# MPPT.net
KiCad netlist of a schematic drawn in Altium Designer
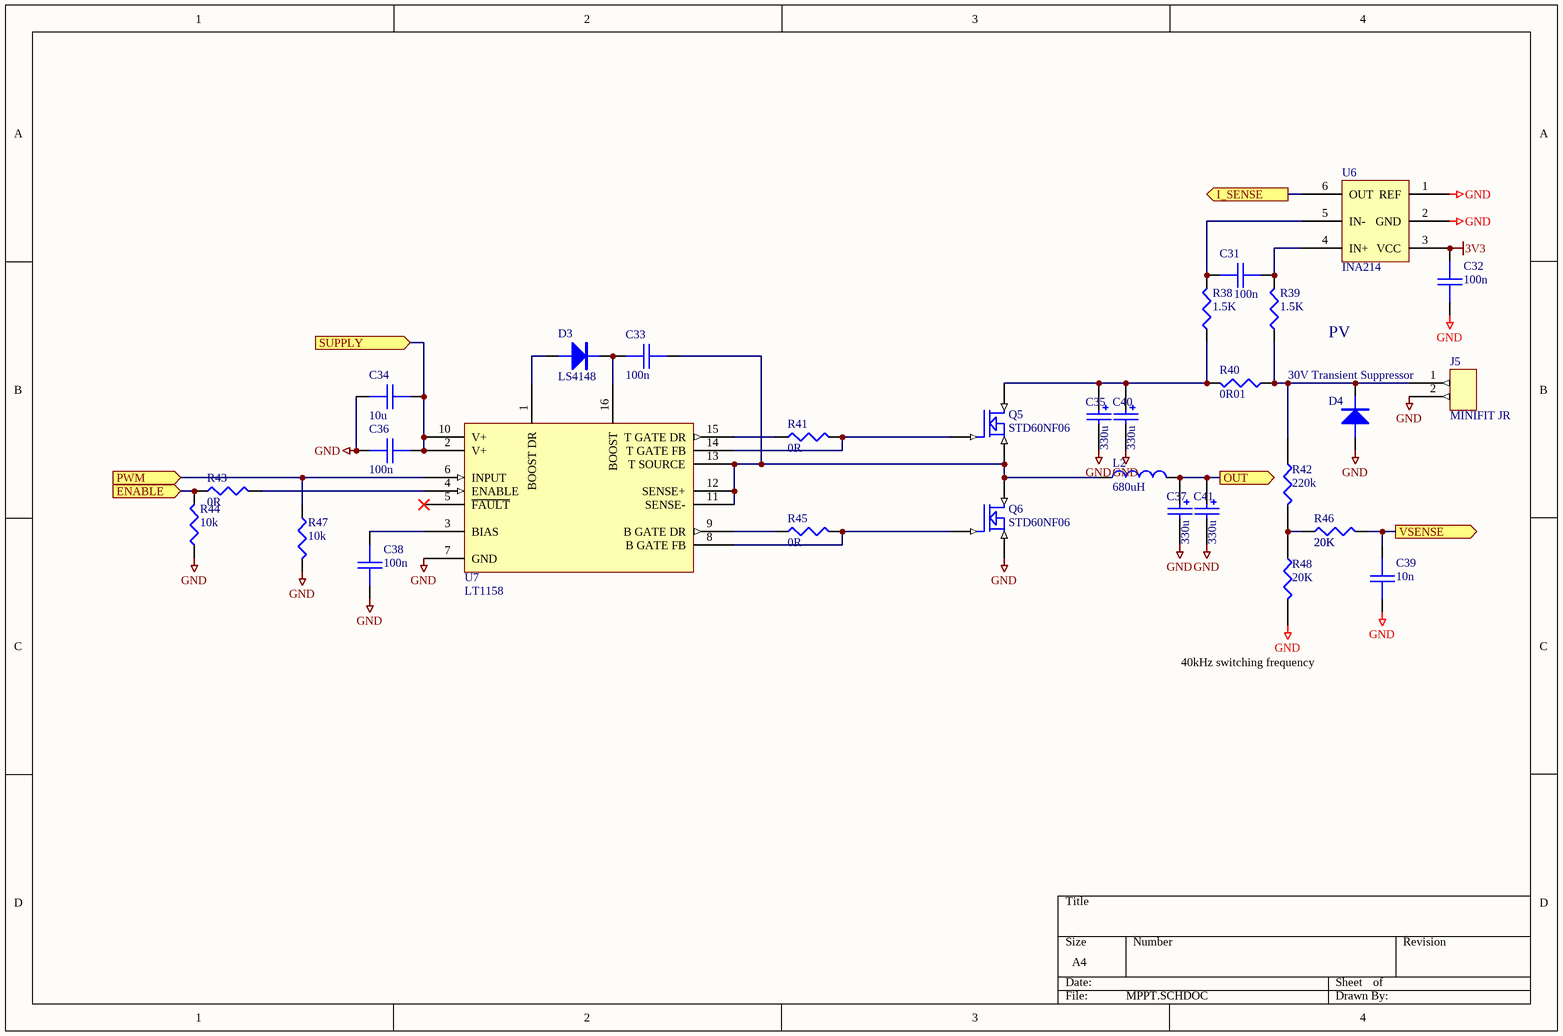
[diagram p0: MPPT.SCHDOC]

(export (version "E")
  (design (tool "Eeschema 10.0.6"))
  (components
    (comp (ref "C31")
      (value "100n")
      (footprint "0603")
      (description "Capacitor")
      (libsource (lib "RCLDQ") (part "CAP"))
    )
    (comp (ref "C32")
      (value "100n")
      (footprint "0603")
      (description "Capacitor")
      (libsource (lib "RCLDQ") (part "CAP"))
    )
    (comp (ref "C33")
      (value "100n")
      (footprint "0603")
      (description "Capacitor")
      (libsource (lib "RCLDQ") (part "CAP"))
    )
    (comp (ref "C34")
      (value "10u")
      (footprint "1206")
      (description "Capacitor")
      (libsource (lib "RCLDQ") (part "CAP"))
    )
    (comp (ref "C35")
      (value "330u")
      (footprint "RAD0.2")
      (description "Polarized Capacitor (Surface Mount)")
      (libsource (lib "RCLDQ") (part "CAP POL3"))
    )
    (comp (ref "C36")
      (value "100n")
      (footprint "0603")
      (description "Capacitor")
      (libsource (lib "RCLDQ") (part "CAP"))
    )
    (comp (ref "C37")
      (value "330u")
      (footprint "RAD0.2")
      (description "Polarized Capacitor (Surface Mount)")
      (libsource (lib "RCLDQ") (part "CAP POL3"))
    )
    (comp (ref "C38")
      (value "100n")
      (footprint "0603")
      (description "Capacitor")
      (libsource (lib "RCLDQ") (part "CAP"))
    )
    (comp (ref "C39")
      (value "10n")
      (footprint "0603")
      (description "Capacitor")
      (libsource (lib "RCLDQ") (part "CAP"))
    )
    (comp (ref "C40")
      (value "330u")
      (footprint "RAD0.2")
      (description "Polarized Capacitor (Surface Mount)")
      (libsource (lib "RCLDQ") (part "CAP POL3"))
    )
    (comp (ref "C41")
      (value "330u")
      (footprint "RAD0.2")
      (description "Polarized Capacitor (Surface Mount)")
      (libsource (lib "RCLDQ") (part "CAP POL3"))
    )
    (comp (ref "D3")
      (value "LS4148")
      (footprint "QMELF")
      (description "Diode")
      (libsource (lib "RCLDQ") (part "DIODE"))
    )
    (comp (ref "D4")
      (value "30V Transient Suppressor")
      (footprint "SMA")
      (description "Diode")
      (libsource (lib "RCLDQ") (part "DIODE"))
    )
    (comp (ref "J5")
      (value "MINIFIT JR")
      (footprint "MINIFITJR-2")
      (libsource (lib "Connectors") (part "CON2"))
    )
    (comp (ref "L2")
      (value "680uH")
      (footprint "Bourns2321-V-RC")
      (description "Inductor")
      (libsource (lib "Miscellaneous Devices") (part "Inductor"))
    )
    (comp (ref "Q5")
      (value "STD60NF06")
      (footprint "DPAK(3)")
      (description "Power MOSFET")
      (libsource (lib "RCLDQ") (part "STD60NF06"))
    )
    (comp (ref "Q6")
      (value "STD60NF06")
      (footprint "DPAK(3)")
      (description "Power MOSFET")
      (libsource (lib "RCLDQ") (part "STD60NF06"))
    )
    (comp (ref "R38")
      (value "1.5K")
      (footprint "0603")
      (description "Resistor")
      (libsource (lib "RCLDQ") (part "RES1"))
    )
    (comp (ref "R39")
      (value "1.5K")
      (footprint "0603")
      (description "Resistor")
      (libsource (lib "RCLDQ") (part "RES1"))
    )
    (comp (ref "R40")
      (value "0R01")
      (footprint "2010")
      (description "Resistor")
      (libsource (lib "RCLDQ") (part "RES1"))
    )
    (comp (ref "R41")
      (value "0R")
      (footprint "0603")
      (description "Resistor")
      (libsource (lib "RCLDQ") (part "RES1"))
    )
    (comp (ref "R42") (value "220k") (footprint "1206") (libsource (lib "*") (part "RES1")))
    (comp (ref "R43")
      (value "0R")
      (footprint "0603")
      (description "Resistor")
      (libsource (lib "RCLDQ") (part "RES1"))
    )
    (comp (ref "R44")
      (value "10k")
      (footprint "0603")
      (description "Resistor")
      (libsource (lib "RCLDQ") (part "RES1"))
    )
    (comp (ref "R45")
      (value "0R")
      (footprint "0603")
      (description "Resistor")
      (libsource (lib "RCLDQ") (part "RES1"))
    )
    (comp (ref "R46")
      (value "20K")
      (footprint "0603")
      (description "Resistor")
      (libsource (lib "RCLDQ") (part "RES1"))
    )
    (comp (ref "R47")
      (value "10k")
      (footprint "0603")
      (description "Resistor")
      (libsource (lib "RCLDQ") (part "RES1"))
    )
    (comp (ref "R48") (value "20K") (footprint "1206") (libsource (lib "*") (part "RES1")))
    (comp (ref "U6")
      (value "INA214")
      (footprint "SC70-6")
      (description "High / Low side Current Sensor")
      (libsource (lib "MiscellaneousIC") (part "INA214"))
    )
    (comp (ref "U7") (value "LT1158") (footprint "SOL16") (libsource (lib "MiscellaneousIC") (part "LT1158")))
  )
  (nets
    (net (code "1") (name "/ENABLE") (class "Default")
      (node (ref "R43") (pin "1") (pinfunction "1_1") (pintype "passive"))
      (node (ref "R44") (pin "2") (pinfunction "2_2") (pintype "passive"))
    )
    (net (code "2") (name "/I_SENSE") (class "Default")
      (node (ref "U6") (pin "6") (pinfunction "OUT_6") (pintype "passive"))
    )
    (net (code "3") (name "/OUT") (class "Default")
      (node (ref "C37") (pin "1") (pinfunction "1_1") (pintype "passive"))
      (node (ref "C41") (pin "1") (pinfunction "1_1") (pintype "passive"))
      (node (ref "L2") (pin "2") (pinfunction "2_2") (pintype "passive"))
    )
    (net (code "4") (name "/PWM") (class "Default")
      (node (ref "R47") (pin "1") (pinfunction "1_1") (pintype "passive"))
      (node (ref "U7") (pin "6") (pinfunction "INPUT_6") (pintype "input"))
    )
    (net (code "5") (name "/SUPPLY") (class "Default")
      (node (ref "C34") (pin "2") (pinfunction "2_2") (pintype "passive"))
      (node (ref "C36") (pin "1") (pinfunction "1_1") (pintype "passive"))
      (node (ref "U7") (pin "10") (pinfunction "V+_10") (pintype "power_in"))
      (node (ref "U7") (pin "2") (pinfunction "V+_2") (pintype "power_in"))
    )
    (net (code "6") (name "/VSENSE") (class "Default")
      (node (ref "C39") (pin "1") (pinfunction "1_1") (pintype "passive"))
      (node (ref "R46") (pin "2") (pinfunction "2_2") (pintype "passive"))
    )
    (net (code "7") (name "3V3") (class "Default")
      (node (ref "C32") (pin "2") (pinfunction "2_2") (pintype "passive"))
      (node (ref "U6") (pin "3") (pinfunction "VCC_3") (pintype "passive"))
    )
    (net (code "8") (name "GND") (class "Default")
      (node (ref "C32") (pin "1") (pinfunction "1_1") (pintype "passive"))
      (node (ref "C34") (pin "1") (pinfunction "1_1") (pintype "passive"))
      (node (ref "C35") (pin "2") (pinfunction "2_2") (pintype "passive"))
      (node (ref "C36") (pin "2") (pinfunction "2_2") (pintype "passive"))
      (node (ref "C37") (pin "2") (pinfunction "2_2") (pintype "passive"))
      (node (ref "C38") (pin "2") (pinfunction "2_2") (pintype "passive"))
      (node (ref "C39") (pin "2") (pinfunction "2_2") (pintype "passive"))
      (node (ref "C40") (pin "2") (pinfunction "2_2") (pintype "passive"))
      (node (ref "C41") (pin "2") (pinfunction "2_2") (pintype "passive"))
      (node (ref "D4") (pin "A") (pinfunction "A_A") (pintype "passive"))
      (node (ref "J5") (pin "2") (pinfunction "2_2") (pintype "output"))
      (node (ref "Q6") (pin "3") (pinfunction "S_3") (pintype "input"))
      (node (ref "R44") (pin "1") (pinfunction "1_1") (pintype "passive"))
      (node (ref "R47") (pin "2") (pinfunction "2_2") (pintype "passive"))
      (node (ref "R48") (pin "2") (pinfunction "2_2") (pintype "passive"))
      (node (ref "U6") (pin "1") (pinfunction "REF_1") (pintype "passive"))
      (node (ref "U6") (pin "2") (pinfunction "GND_2") (pintype "passive"))
      (node (ref "U7") (pin "7") (pinfunction "GND_7") (pintype "power_in"))
    )
    (net (code "9") (name "Net-(D4-PadK)") (class "Default")
      (node (ref "D4") (pin "K") (pinfunction "K_K") (pintype "passive"))
      (node (ref "J5") (pin "1") (pinfunction "1_1") (pintype "output"))
      (node (ref "R39") (pin "1") (pinfunction "1_1") (pintype "passive"))
      (node (ref "R40") (pin "1") (pinfunction "1_1") (pintype "passive"))
      (node (ref "R42") (pin "1") (pinfunction "1_1") (pintype "passive"))
    )
    (net (code "10") (name "Net-(Q5-D)") (class "Default")
      (node (ref "C35") (pin "1") (pinfunction "1_1") (pintype "passive"))
      (node (ref "C40") (pin "1") (pinfunction "1_1") (pintype "passive"))
      (node (ref "Q5") (pin "2") (pinfunction "D_2") (pintype "input"))
      (node (ref "R38") (pin "1") (pinfunction "1_1") (pintype "passive"))
      (node (ref "R40") (pin "2") (pinfunction "2_2") (pintype "passive"))
    )
    (net (code "11") (name "Net-(Q5-G)") (class "Default")
      (node (ref "Q5") (pin "1") (pinfunction "G_1") (pintype "input"))
      (node (ref "R41") (pin "2") (pinfunction "2_2") (pintype "passive"))
      (node (ref "U7") (pin "14") (pinfunction "T_GATE_FB_14") (pintype "passive"))
    )
    (net (code "12") (name "Net-(Q5-S)") (class "Default")
      (node (ref "C33") (pin "2") (pinfunction "2_2") (pintype "passive"))
      (node (ref "L2") (pin "1") (pinfunction "1_1") (pintype "passive"))
      (node (ref "Q5") (pin "3") (pinfunction "S_3") (pintype "input"))
      (node (ref "Q6") (pin "2") (pinfunction "D_2") (pintype "input"))
      (node (ref "U7") (pin "11") (pinfunction "SENSE-_11") (pintype "passive"))
      (node (ref "U7") (pin "12") (pinfunction "SENSE+_12") (pintype "passive"))
      (node (ref "U7") (pin "13") (pinfunction "T_SOURCE_13") (pintype "passive"))
    )
    (net (code "13") (name "Net-(Q6-G)") (class "Default")
      (node (ref "Q6") (pin "1") (pinfunction "G_1") (pintype "input"))
      (node (ref "R45") (pin "2") (pinfunction "2_2") (pintype "passive"))
      (node (ref "U7") (pin "8") (pinfunction "B_GATE_FB_8") (pintype "passive"))
    )
    (net (code "14") (name "Net-(R42-Pad2)") (class "Default")
      (node (ref "R42") (pin "2") (pinfunction "2_2") (pintype "passive"))
      (node (ref "R46") (pin "1") (pinfunction "1_1") (pintype "passive"))
      (node (ref "R48") (pin "1") (pinfunction "1_1") (pintype "passive"))
    )
    (net (code "15") (name "Net-(U6-IN+)") (class "Default")
      (node (ref "C31") (pin "2") (pinfunction "2_2") (pintype "passive"))
      (node (ref "R39") (pin "2") (pinfunction "2_2") (pintype "passive"))
      (node (ref "U6") (pin "4") (pinfunction "IN+_4") (pintype "passive"))
    )
    (net (code "16") (name "Net-(U6-IN-)") (class "Default")
      (node (ref "C31") (pin "1") (pinfunction "1_1") (pintype "passive"))
      (node (ref "R38") (pin "2") (pinfunction "2_2") (pintype "passive"))
      (node (ref "U6") (pin "5") (pinfunction "IN-_5") (pintype "passive"))
    )
    (net (code "17") (name "Net-(U7-BIAS)") (class "Default")
      (node (ref "C38") (pin "1") (pinfunction "1_1") (pintype "passive"))
      (node (ref "U7") (pin "3") (pinfunction "BIAS_3") (pintype "passive"))
    )
    (net (code "18") (name "Net-(U7-BOOST)") (class "Default")
      (node (ref "C33") (pin "1") (pinfunction "1_1") (pintype "passive"))
      (node (ref "D3") (pin "K") (pinfunction "K_K") (pintype "passive"))
      (node (ref "U7") (pin "16") (pinfunction "BOOST_16") (pintype "power_in"))
    )
    (net (code "19") (name "Net-(U7-BOOST_DR)") (class "Default")
      (node (ref "D3") (pin "A") (pinfunction "A_A") (pintype "passive"))
      (node (ref "U7") (pin "1") (pinfunction "BOOST_DR_1") (pintype "power_in"))
    )
    (net (code "20") (name "Net-(U7-B_GATE_DR)") (class "Default")
      (node (ref "R45") (pin "1") (pinfunction "1_1") (pintype "passive"))
      (node (ref "U7") (pin "9") (pinfunction "B_GATE_DR_9") (pintype "output"))
    )
    (net (code "21") (name "Net-(U7-ENABLE)") (class "Default")
      (node (ref "R43") (pin "2") (pinfunction "2_2") (pintype "passive"))
      (node (ref "U7") (pin "4") (pinfunction "ENABLE_4") (pintype "input"))
    )
    (net (code "22") (name "Net-(U7-T_GATE_DR)") (class "Default")
      (node (ref "R41") (pin "1") (pinfunction "1_1") (pintype "passive"))
      (node (ref "U7") (pin "15") (pinfunction "T_GATE_DR_15") (pintype "output"))
    )
    (net (code "23") (name "unconnected-(U7-~{FAULT}-Pad5)") (class "Default")
      (node (ref "U7") (pin "5") (pinfunction "~{FAULT}_5") (pintype "open_collector+no_connect"))
    )
  )
)
